# Carte1.net
KiCad netlist of a schematic drawn in Altium Designer
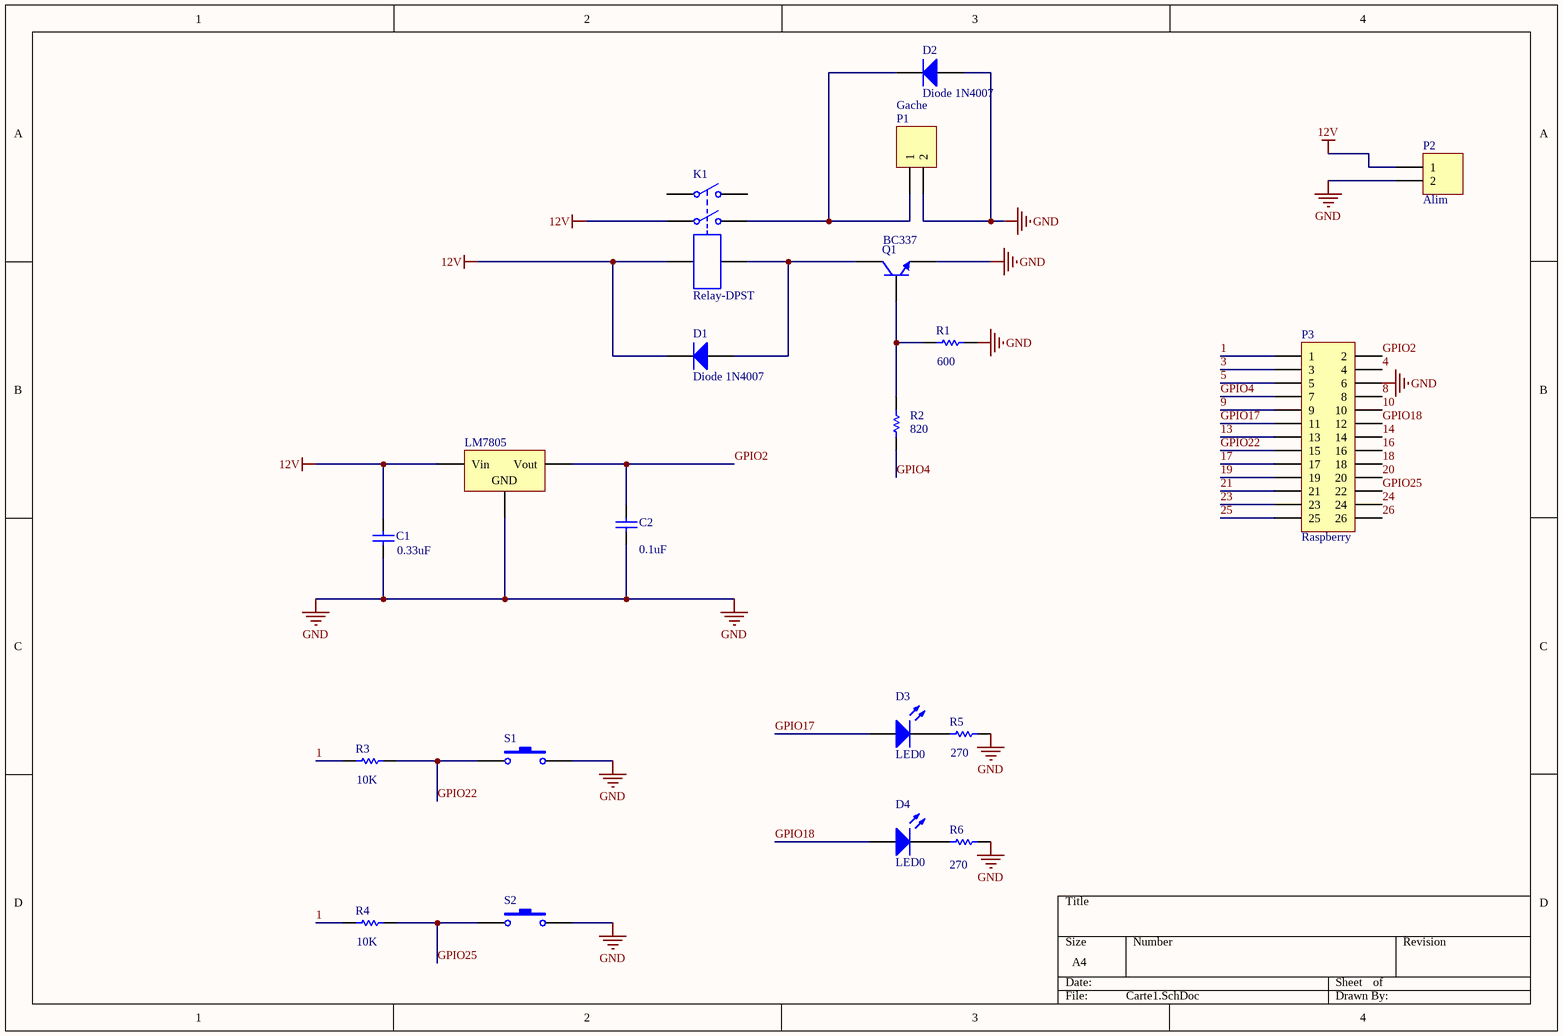
[diagram p0: Carte1.SchDoc]

(export (version "E")
  (design (tool "Eeschema 10.0.6"))
  (components
    (comp (ref "C1")
      (value "0.33uF")
      (footprint "RAD-0.2")
      (description "Capacitor")
      (fields (field (name "PUBLISHER") "Altium Limited"))
      (libsource (lib "Miscellaneous Devices") (part "Cap"))
    )
    (comp (ref "C2")
      (value "0.1uF")
      (footprint "RAD-0.2")
      (description "Capacitor")
      (fields (field (name "PUBLISHER") "Altium Limited"))
      (libsource (lib "Miscellaneous Devices") (part "Cap"))
    )
    (comp (ref "D1")
      (value "Diode 1N4007")
      (footprint "DIODE-0.4")
      (description "1 Amp General Purpose Rectifier")
      (fields (field (name "PUBLISHER") "Altium Limited"))
      (libsource (lib "Miscellaneous Devices") (part "Diode 1N4007"))
    )
    (comp (ref "D2")
      (value "Diode 1N4007")
      (footprint "DIODE-0.4")
      (description "1 Amp General Purpose Rectifier")
      (fields (field (name "PUBLISHER") "Altium Limited"))
      (libsource (lib "Miscellaneous Devices") (part "Diode 1N4007"))
    )
    (comp (ref "D3")
      (value "LED0")
      (footprint "LED")
      (description "Typical INFRARED GaAs LED")
      (fields (field (name "PUBLISHER") "Altium Limited"))
      (libsource (lib "Miscellaneous Devices") (part "LED0"))
    )
    (comp (ref "D4")
      (value "LED0")
      (footprint "LED")
      (description "Typical INFRARED GaAs LED")
      (fields (field (name "PUBLISHER") "Altium Limited"))
      (libsource (lib "Miscellaneous Devices") (part "LED0"))
    )
    (comp (ref "K1")
      (value "Relay-DPST")
      (footprint "Relais1")
      (description "Dual-Pole Single-Throw Relay")
      (fields (field (name "PUBLISHER") "Altium Limited"))
      (libsource (lib "Miscellaneous Devices") (part "Relay-DPST"))
    )
    (comp (ref "LM7805")
      (value "~")
      (footprint "TO220V")
      (description "Voltage Regulator")
      (fields (field (name "PUBLISHER") "Altium Limited"))
      (libsource (lib "Miscellaneous Devices") (part "Volt Reg"))
    )
    (comp (ref "P1")
      (value "Gache")
      (footprint "BORN5-2")
      (description "Header, 2-Pin")
      (fields (field (name "PUBLISHER") "Altium Limited"))
      (libsource (lib "") (part "Header 2_1"))
    )
    (comp (ref "P2")
      (value "Alim")
      (footprint "BORN5-2")
      (description "Header, 2-Pin")
      (fields (field (name "PUBLISHER") "Altium Limited"))
      (libsource (lib "Miscellaneous Connectors") (part "Header 2"))
    )
    (comp (ref "P3")
      (value "Raspberry")
      (footprint "DIP-20")
      (description "Header, 13-Pin, Dual row")
      (fields (field (name "PUBLISHER") "Altium Limited"))
      (libsource (lib "Miscellaneous Connectors") (part "MHDR2X13"))
    )
    (comp (ref "Q1")
      (value "BC337")
      (footprint "TO92-2")
      (description "NPN General Purpose Amplifier")
      (fields (field (name "PUBLISHER") "Altium Limited"))
      (libsource (lib "Miscellaneous Devices") (part "2N3904"))
    )
    (comp (ref "R1")
      (value "600")
      (footprint "AXIAL-0.5")
      (description "Resistor")
      (fields (field (name "PUBLISHER") "Altium Limited"))
      (libsource (lib "Miscellaneous Devices") (part "Res1"))
    )
    (comp (ref "R2")
      (value "820")
      (footprint "AXIAL-0.5")
      (description "Resistor")
      (fields (field (name "PUBLISHER") "Altium Limited"))
      (libsource (lib "Miscellaneous Devices") (part "Res1"))
    )
    (comp (ref "R3")
      (value "10K")
      (footprint "AXIAL-0.5")
      (description "Resistor")
      (fields (field (name "PUBLISHER") "Altium Limited"))
      (libsource (lib "Miscellaneous Devices") (part "Res1"))
    )
    (comp (ref "R4")
      (value "10K")
      (footprint "AXIAL-0.5")
      (description "Resistor")
      (fields (field (name "PUBLISHER") "Altium Limited"))
      (libsource (lib "Miscellaneous Devices") (part "Res1"))
    )
    (comp (ref "R5")
      (value "270")
      (footprint "AXIAL-0.5")
      (description "Resistor")
      (fields (field (name "PUBLISHER") "Altium Limited"))
      (libsource (lib "Miscellaneous Devices") (part "Res1"))
    )
    (comp (ref "R6")
      (value "270")
      (footprint "AXIAL-0.5")
      (description "Resistor")
      (fields (field (name "PUBLISHER") "Altium Limited"))
      (libsource (lib "Miscellaneous Devices") (part "Res1"))
    )
    (comp (ref "S1")
      (value "~")
      (footprint "BP")
      (description "Switch")
      (fields (field (name "PUBLISHER") "Altium Limited"))
      (libsource (lib "Miscellaneous Devices") (part "SW-PB"))
    )
    (comp (ref "S2")
      (value "~")
      (footprint "BP")
      (description "Switch")
      (fields (field (name "PUBLISHER") "Altium Limited"))
      (libsource (lib "Miscellaneous Devices") (part "SW-PB"))
    )
  )
  (nets
    (net (code "1") (name "/1") (class "Default")
      (node (ref "P3") (pin "1") (pinfunction "1_1") (pintype "passive"))
      (node (ref "R3") (pin "1") (pinfunction "1_1") (pintype "passive"))
      (node (ref "R4") (pin "1") (pinfunction "1_1") (pintype "passive"))
    )
    (net (code "2") (name "/3") (class "Default")
      (node (ref "P3") (pin "3") (pinfunction "3_3") (pintype "passive"))
    )
    (net (code "3") (name "/4") (class "Default")
      (node (ref "P3") (pin "4") (pinfunction "4_4") (pintype "passive"))
    )
    (net (code "4") (name "/5") (class "Default")
      (node (ref "P3") (pin "5") (pinfunction "5_5") (pintype "passive"))
    )
    (net (code "5") (name "/8") (class "Default")
      (node (ref "P3") (pin "8") (pinfunction "8_8") (pintype "passive"))
    )
    (net (code "6") (name "/9") (class "Default")
      (node (ref "P3") (pin "9") (pinfunction "9_9") (pintype "passive"))
    )
    (net (code "7") (name "/10") (class "Default")
      (node (ref "P3") (pin "10") (pinfunction "10_10") (pintype "passive"))
    )
    (net (code "8") (name "/13") (class "Default")
      (node (ref "P3") (pin "13") (pinfunction "13_13") (pintype "passive"))
    )
    (net (code "9") (name "/14") (class "Default")
      (node (ref "P3") (pin "14") (pinfunction "14_14") (pintype "passive"))
    )
    (net (code "10") (name "/16") (class "Default")
      (node (ref "P3") (pin "16") (pinfunction "16_16") (pintype "passive"))
    )
    (net (code "11") (name "/17") (class "Default")
      (node (ref "P3") (pin "17") (pinfunction "17_17") (pintype "passive"))
    )
    (net (code "12") (name "/18") (class "Default")
      (node (ref "P3") (pin "18") (pinfunction "18_18") (pintype "passive"))
    )
    (net (code "13") (name "/19") (class "Default")
      (node (ref "P3") (pin "19") (pinfunction "19_19") (pintype "passive"))
    )
    (net (code "14") (name "/20") (class "Default")
      (node (ref "P3") (pin "20") (pinfunction "20_20") (pintype "passive"))
    )
    (net (code "15") (name "/21") (class "Default")
      (node (ref "P3") (pin "21") (pinfunction "21_21") (pintype "passive"))
    )
    (net (code "16") (name "/23") (class "Default")
      (node (ref "P3") (pin "23") (pinfunction "23_23") (pintype "passive"))
    )
    (net (code "17") (name "/24") (class "Default")
      (node (ref "P3") (pin "24") (pinfunction "24_24") (pintype "passive"))
    )
    (net (code "18") (name "/25") (class "Default")
      (node (ref "P3") (pin "25") (pinfunction "25_25") (pintype "passive"))
    )
    (net (code "19") (name "/26") (class "Default")
      (node (ref "P3") (pin "26") (pinfunction "26_26") (pintype "passive"))
    )
    (net (code "20") (name "/GPIO2") (class "Default")
      (node (ref "C2") (pin "2") (pinfunction "2_2") (pintype "passive"))
      (node (ref "LM7805") (pin "3") (pinfunction "Vout_3") (pintype "passive"))
      (node (ref "P3") (pin "2") (pinfunction "2_2") (pintype "passive"))
    )
    (net (code "21") (name "/GPIO4") (class "Default")
      (node (ref "P3") (pin "7") (pinfunction "7_7") (pintype "passive"))
      (node (ref "R2") (pin "1") (pinfunction "1_1") (pintype "passive"))
    )
    (net (code "22") (name "/GPIO17") (class "Default")
      (node (ref "D3") (pin "1") (pinfunction "A_1") (pintype "passive"))
      (node (ref "P3") (pin "11") (pinfunction "11_11") (pintype "passive"))
    )
    (net (code "23") (name "/GPIO18") (class "Default")
      (node (ref "D4") (pin "1") (pinfunction "A_1") (pintype "passive"))
      (node (ref "P3") (pin "12") (pinfunction "12_12") (pintype "passive"))
    )
    (net (code "24") (name "/GPIO22") (class "Default")
      (node (ref "P3") (pin "15") (pinfunction "15_15") (pintype "passive"))
      (node (ref "R3") (pin "2") (pinfunction "2_2") (pintype "passive"))
      (node (ref "S1") (pin "1") (pinfunction "1_1") (pintype "passive"))
    )
    (net (code "25") (name "/GPIO25") (class "Default")
      (node (ref "P3") (pin "22") (pinfunction "22_22") (pintype "passive"))
      (node (ref "R4") (pin "2") (pinfunction "2_2") (pintype "passive"))
      (node (ref "S2") (pin "1") (pinfunction "1_1") (pintype "passive"))
    )
    (net (code "26") (name "12V") (class "Default")
      (node (ref "C1") (pin "2") (pinfunction "2_2") (pintype "passive"))
      (node (ref "D1") (pin "2") (pinfunction "K_2") (pintype "passive"))
      (node (ref "K1") (pin "3") (pinfunction "3_3") (pintype "passive"))
      (node (ref "K1") (pin "5") (pinfunction "5_5") (pintype "passive"))
      (node (ref "LM7805") (pin "1") (pinfunction "Vin_1") (pintype "passive"))
      (node (ref "P2") (pin "1") (pinfunction "1_1") (pintype "passive"))
    )
    (net (code "27") (name "GND") (class "Default")
      (node (ref "C1") (pin "1") (pinfunction "1_1") (pintype "passive"))
      (node (ref "C2") (pin "1") (pinfunction "1_1") (pintype "passive"))
      (node (ref "D2") (pin "1") (pinfunction "A_1") (pintype "passive"))
      (node (ref "LM7805") (pin "2") (pinfunction "GND_2") (pintype "passive"))
      (node (ref "P1") (pin "2") (pinfunction "2_2") (pintype "passive"))
      (node (ref "P2") (pin "2") (pinfunction "2_2") (pintype "passive"))
      (node (ref "P3") (pin "6") (pinfunction "6_6") (pintype "passive"))
      (node (ref "Q1") (pin "1") (pinfunction "E_1") (pintype "passive"))
      (node (ref "R1") (pin "2") (pinfunction "2_2") (pintype "passive"))
      (node (ref "R5") (pin "2") (pinfunction "2_2") (pintype "passive"))
      (node (ref "R6") (pin "2") (pinfunction "2_2") (pintype "passive"))
      (node (ref "S1") (pin "2") (pinfunction "2_2") (pintype "passive"))
      (node (ref "S2") (pin "2") (pinfunction "2_2") (pintype "passive"))
    )
    (net (code "28") (name "Net-(D1-A)") (class "Default")
      (node (ref "D1") (pin "1") (pinfunction "A_1") (pintype "passive"))
      (node (ref "K1") (pin "6") (pinfunction "6_6") (pintype "passive"))
      (node (ref "Q1") (pin "3") (pinfunction "C_3") (pintype "passive"))
    )
    (net (code "29") (name "Net-(D2-K)") (class "Default")
      (node (ref "D2") (pin "2") (pinfunction "K_2") (pintype "passive"))
      (node (ref "K1") (pin "4") (pinfunction "4_4") (pintype "passive"))
      (node (ref "P1") (pin "1") (pinfunction "1_1") (pintype "passive"))
    )
    (net (code "30") (name "Net-(D3-K)") (class "Default")
      (node (ref "D3") (pin "2") (pinfunction "K_2") (pintype "passive"))
      (node (ref "R5") (pin "1") (pinfunction "1_1") (pintype "passive"))
    )
    (net (code "31") (name "Net-(D4-K)") (class "Default")
      (node (ref "D4") (pin "2") (pinfunction "K_2") (pintype "passive"))
      (node (ref "R6") (pin "1") (pinfunction "1_1") (pintype "passive"))
    )
    (net (code "32") (name "Net-(Q1-B)") (class "Default")
      (node (ref "Q1") (pin "2") (pinfunction "B_2") (pintype "passive"))
      (node (ref "R1") (pin "1") (pinfunction "1_1") (pintype "passive"))
      (node (ref "R2") (pin "2") (pinfunction "2_2") (pintype "passive"))
    )
    (net (code "33") (name "unconnected-(K1-Pad1)") (class "Default")
      (node (ref "K1") (pin "1") (pinfunction "1_1") (pintype "passive"))
    )
    (net (code "34") (name "unconnected-(K1-Pad2)") (class "Default")
      (node (ref "K1") (pin "2") (pinfunction "2_2") (pintype "passive"))
    )
  )
)
